# Module_I2C_Amiga_Floppy.net
KiCad netlist of a schematic drawn in EAGLE
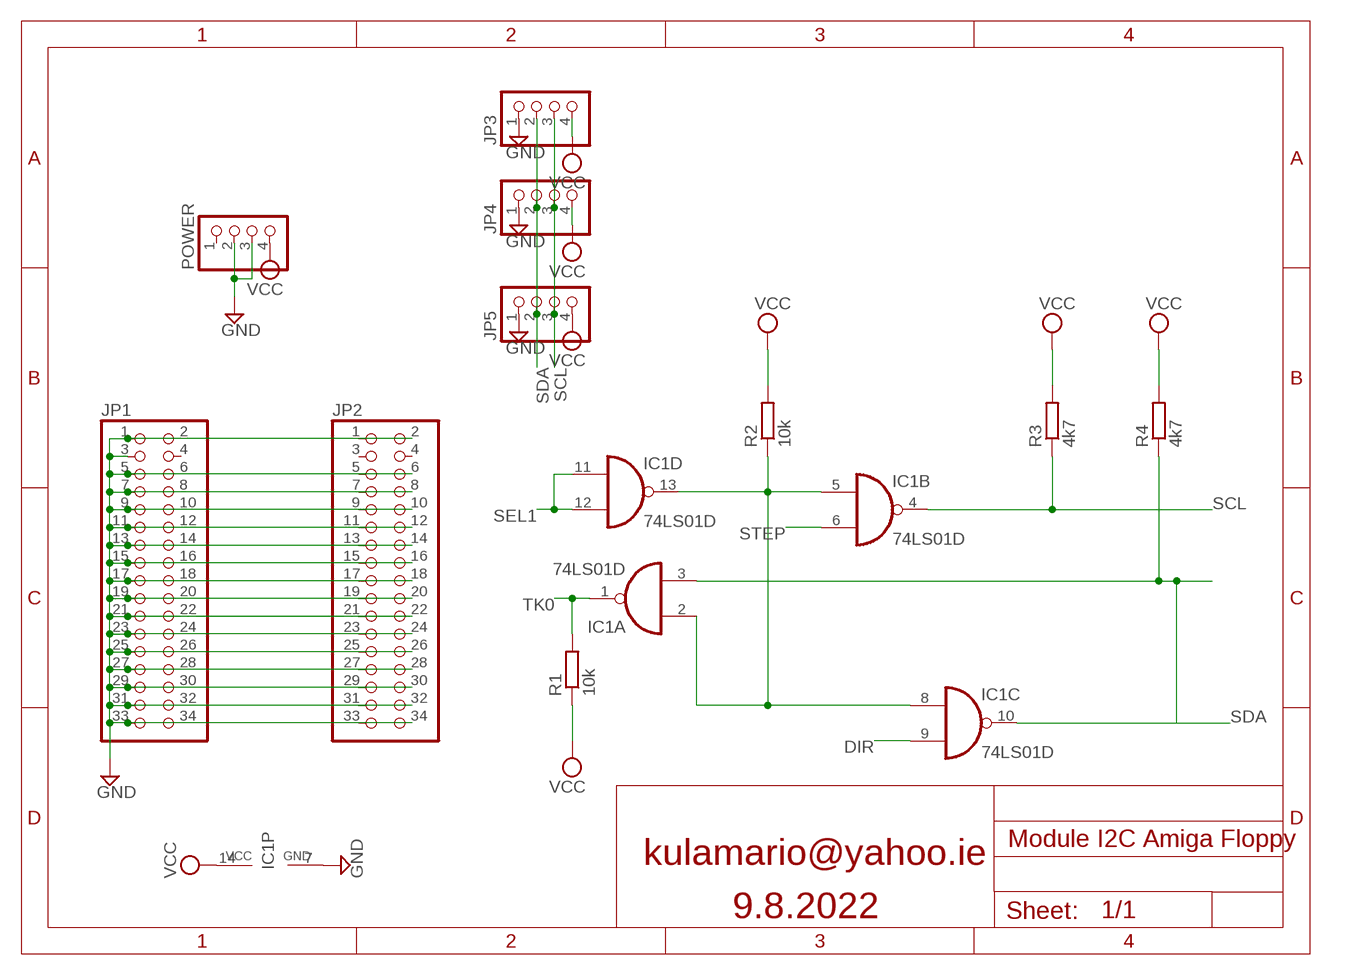
[diagram p0: schematic, sheet 1]

(export (version "E")
  (design (tool "Eeschema 10.0.6"))
  (components
    (comp (ref "IC1")
      (value "74LS01D")
      (footprint "eagle-import:SO14")
      (libsource (lib "eagle-import") (part "7401DLS"))
    )
    (comp (ref "JP1")
      (value "PINHD-2X17")
      (footprint "eagle-import:2X17")
      (libsource (lib "eagle-import") (part "PINHD-2X17"))
    )
    (comp (ref "JP2")
      (value "PINHD-2X17")
      (footprint "eagle-import:2X17")
      (libsource (lib "eagle-import") (part "PINHD-2X17"))
    )
    (comp (ref "JP3")
      (value "PINHD-1X4")
      (footprint "eagle-import:1X04")
      (libsource (lib "eagle-import") (part "PINHD-1X4"))
    )
    (comp (ref "JP4")
      (value "PINHD-1X4")
      (footprint "eagle-import:1X04")
      (libsource (lib "eagle-import") (part "PINHD-1X4"))
    )
    (comp (ref "JP5")
      (value "PINHD-1X4")
      (footprint "eagle-import:1X04")
      (libsource (lib "eagle-import") (part "PINHD-1X4"))
    )
    (comp (ref "POWER")
      (value "PINHD-1X4")
      (footprint "eagle-import:1X04")
      (libsource (lib "eagle-import") (part "PINHD-1X4"))
    )
    (comp (ref "R1")
      (value "10k")
      (footprint "eagle-import:R0805")
      (libsource (lib "eagle-import") (part "R-EU_R0805"))
    )
    (comp (ref "R2")
      (value "10k")
      (footprint "eagle-import:R0805")
      (libsource (lib "eagle-import") (part "R-EU_R0805"))
    )
    (comp (ref "R3")
      (value "4k7")
      (footprint "eagle-import:R0805")
      (libsource (lib "eagle-import") (part "R-EU_R0805"))
    )
    (comp (ref "R4")
      (value "4k7")
      (footprint "eagle-import:R0805")
      (libsource (lib "eagle-import") (part "R-EU_R0805"))
    )
  )
  (nets
    (net (code "1") (name "/DIR") (class "Default")
      (node (ref "IC1") (pin "9") (pinfunction "I1_9") (pintype "input"))
      (node (ref "JP1") (pin "18") (pinfunction "18_18") (pintype "passive"))
      (node (ref "JP2") (pin "18") (pinfunction "18_18") (pintype "passive"))
    )
    (net (code "2") (name "/SCL") (class "Default")
      (node (ref "IC1") (pin "4") (pinfunction "O_4") (pintype "open_collector"))
      (node (ref "JP3") (pin "3") (pinfunction "3_3") (pintype "passive"))
      (node (ref "JP4") (pin "3") (pinfunction "3_3") (pintype "passive"))
      (node (ref "JP5") (pin "3") (pinfunction "3_3") (pintype "passive"))
      (node (ref "R3") (pin "1") (pinfunction "1_1") (pintype "passive"))
    )
    (net (code "3") (name "/SDA") (class "Default")
      (node (ref "IC1") (pin "10") (pinfunction "O_10") (pintype "open_collector"))
      (node (ref "IC1") (pin "3") (pinfunction "I1_3") (pintype "input"))
      (node (ref "JP3") (pin "2") (pinfunction "2_2") (pintype "passive"))
      (node (ref "JP4") (pin "2") (pinfunction "2_2") (pintype "passive"))
      (node (ref "JP5") (pin "2") (pinfunction "2_2") (pintype "passive"))
      (node (ref "R4") (pin "1") (pinfunction "1_1") (pintype "passive"))
    )
    (net (code "4") (name "/SEL1") (class "Default")
      (node (ref "IC1") (pin "11") (pinfunction "I0_11") (pintype "input"))
      (node (ref "IC1") (pin "12") (pinfunction "I1_12") (pintype "input"))
      (node (ref "JP1") (pin "12") (pinfunction "12_12") (pintype "passive"))
      (node (ref "JP2") (pin "12") (pinfunction "12_12") (pintype "passive"))
    )
    (net (code "5") (name "/STEP") (class "Default")
      (node (ref "IC1") (pin "6") (pinfunction "I1_6") (pintype "input"))
      (node (ref "JP1") (pin "20") (pinfunction "20_20") (pintype "passive"))
      (node (ref "JP2") (pin "20") (pinfunction "20_20") (pintype "passive"))
    )
    (net (code "6") (name "/TK0") (class "Default")
      (node (ref "IC1") (pin "1") (pinfunction "O_1") (pintype "open_collector"))
      (node (ref "JP1") (pin "26") (pinfunction "26_26") (pintype "passive"))
      (node (ref "JP2") (pin "26") (pinfunction "26_26") (pintype "passive"))
      (node (ref "R1") (pin "2") (pinfunction "2_2") (pintype "passive"))
    )
    (net (code "7") (name "GND") (class "Default")
      (node (ref "IC1") (pin "7") (pinfunction "GND_7") (pintype "power_in"))
      (node (ref "JP1") (pin "1") (pinfunction "1_1") (pintype "passive"))
      (node (ref "JP1") (pin "11") (pinfunction "11_11") (pintype "passive"))
      (node (ref "JP1") (pin "13") (pinfunction "13_13") (pintype "passive"))
      (node (ref "JP1") (pin "15") (pinfunction "15_15") (pintype "passive"))
      (node (ref "JP1") (pin "17") (pinfunction "17_17") (pintype "passive"))
      (node (ref "JP1") (pin "19") (pinfunction "19_19") (pintype "passive"))
      (node (ref "JP1") (pin "21") (pinfunction "21_21") (pintype "passive"))
      (node (ref "JP1") (pin "23") (pinfunction "23_23") (pintype "passive"))
      (node (ref "JP1") (pin "25") (pinfunction "25_25") (pintype "passive"))
      (node (ref "JP1") (pin "27") (pinfunction "27_27") (pintype "passive"))
      (node (ref "JP1") (pin "29") (pinfunction "29_29") (pintype "passive"))
      (node (ref "JP1") (pin "3") (pinfunction "3_3") (pintype "passive"))
      (node (ref "JP1") (pin "31") (pinfunction "31_31") (pintype "passive"))
      (node (ref "JP1") (pin "33") (pinfunction "33_33") (pintype "passive"))
      (node (ref "JP1") (pin "5") (pinfunction "5_5") (pintype "passive"))
      (node (ref "JP1") (pin "7") (pinfunction "7_7") (pintype "passive"))
      (node (ref "JP1") (pin "9") (pinfunction "9_9") (pintype "passive"))
      (node (ref "JP2") (pin "1") (pinfunction "1_1") (pintype "passive"))
      (node (ref "JP2") (pin "11") (pinfunction "11_11") (pintype "passive"))
      (node (ref "JP2") (pin "13") (pinfunction "13_13") (pintype "passive"))
      (node (ref "JP2") (pin "15") (pinfunction "15_15") (pintype "passive"))
      (node (ref "JP2") (pin "17") (pinfunction "17_17") (pintype "passive"))
      (node (ref "JP2") (pin "19") (pinfunction "19_19") (pintype "passive"))
      (node (ref "JP2") (pin "21") (pinfunction "21_21") (pintype "passive"))
      (node (ref "JP2") (pin "23") (pinfunction "23_23") (pintype "passive"))
      (node (ref "JP2") (pin "25") (pinfunction "25_25") (pintype "passive"))
      (node (ref "JP2") (pin "27") (pinfunction "27_27") (pintype "passive"))
      (node (ref "JP2") (pin "29") (pinfunction "29_29") (pintype "passive"))
      (node (ref "JP2") (pin "31") (pinfunction "31_31") (pintype "passive"))
      (node (ref "JP2") (pin "33") (pinfunction "33_33") (pintype "passive"))
      (node (ref "JP2") (pin "5") (pinfunction "5_5") (pintype "passive"))
      (node (ref "JP2") (pin "7") (pinfunction "7_7") (pintype "passive"))
      (node (ref "JP2") (pin "9") (pinfunction "9_9") (pintype "passive"))
      (node (ref "JP3") (pin "1") (pinfunction "1_1") (pintype "passive"))
      (node (ref "JP4") (pin "1") (pinfunction "1_1") (pintype "passive"))
      (node (ref "JP5") (pin "1") (pinfunction "1_1") (pintype "passive"))
      (node (ref "POWER") (pin "2") (pinfunction "2_2") (pintype "passive"))
      (node (ref "POWER") (pin "3") (pinfunction "3_3") (pintype "passive"))
    )
    (net (code "8") (name "Net-(IC1A-I0)") (class "Default")
      (node (ref "IC1") (pin "13") (pinfunction "O_13") (pintype "open_collector"))
      (node (ref "IC1") (pin "2") (pinfunction "I0_2") (pintype "input"))
      (node (ref "IC1") (pin "5") (pinfunction "I0_5") (pintype "input"))
      (node (ref "IC1") (pin "8") (pinfunction "I0_8") (pintype "input"))
      (node (ref "R2") (pin "1") (pinfunction "1_1") (pintype "passive"))
    )
    (net (code "9") (name "Net-(JP1-Pad2)") (class "Default")
      (node (ref "JP1") (pin "2") (pinfunction "2_2") (pintype "passive"))
      (node (ref "JP2") (pin "2") (pinfunction "2_2") (pintype "passive"))
    )
    (net (code "10") (name "Net-(JP1-Pad6)") (class "Default")
      (node (ref "JP1") (pin "6") (pinfunction "6_6") (pintype "passive"))
      (node (ref "JP2") (pin "6") (pinfunction "6_6") (pintype "passive"))
    )
    (net (code "11") (name "Net-(JP1-Pad8)") (class "Default")
      (node (ref "JP1") (pin "8") (pinfunction "8_8") (pintype "passive"))
      (node (ref "JP2") (pin "8") (pinfunction "8_8") (pintype "passive"))
    )
    (net (code "12") (name "Net-(JP1-Pad10)") (class "Default")
      (node (ref "JP1") (pin "10") (pinfunction "10_10") (pintype "passive"))
      (node (ref "JP2") (pin "10") (pinfunction "10_10") (pintype "passive"))
    )
    (net (code "13") (name "Net-(JP1-Pad14)") (class "Default")
      (node (ref "JP1") (pin "14") (pinfunction "14_14") (pintype "passive"))
      (node (ref "JP2") (pin "14") (pinfunction "14_14") (pintype "passive"))
    )
    (net (code "14") (name "Net-(JP1-Pad16)") (class "Default")
      (node (ref "JP1") (pin "16") (pinfunction "16_16") (pintype "passive"))
      (node (ref "JP2") (pin "16") (pinfunction "16_16") (pintype "passive"))
    )
    (net (code "15") (name "Net-(JP1-Pad22)") (class "Default")
      (node (ref "JP1") (pin "22") (pinfunction "22_22") (pintype "passive"))
      (node (ref "JP2") (pin "22") (pinfunction "22_22") (pintype "passive"))
    )
    (net (code "16") (name "Net-(JP1-Pad24)") (class "Default")
      (node (ref "JP1") (pin "24") (pinfunction "24_24") (pintype "passive"))
      (node (ref "JP2") (pin "24") (pinfunction "24_24") (pintype "passive"))
    )
    (net (code "17") (name "Net-(JP1-Pad28)") (class "Default")
      (node (ref "JP1") (pin "28") (pinfunction "28_28") (pintype "passive"))
      (node (ref "JP2") (pin "28") (pinfunction "28_28") (pintype "passive"))
    )
    (net (code "18") (name "Net-(JP1-Pad30)") (class "Default")
      (node (ref "JP1") (pin "30") (pinfunction "30_30") (pintype "passive"))
      (node (ref "JP2") (pin "30") (pinfunction "30_30") (pintype "passive"))
    )
    (net (code "19") (name "Net-(JP1-Pad32)") (class "Default")
      (node (ref "JP1") (pin "32") (pinfunction "32_32") (pintype "passive"))
      (node (ref "JP2") (pin "32") (pinfunction "32_32") (pintype "passive"))
    )
    (net (code "20") (name "Net-(JP1-Pad34)") (class "Default")
      (node (ref "JP1") (pin "34") (pinfunction "34_34") (pintype "passive"))
      (node (ref "JP2") (pin "34") (pinfunction "34_34") (pintype "passive"))
    )
    (net (code "21") (name "VCC") (class "Default")
      (node (ref "IC1") (pin "14") (pinfunction "VCC_14") (pintype "power_in"))
      (node (ref "JP3") (pin "4") (pinfunction "4_4") (pintype "passive"))
      (node (ref "JP4") (pin "4") (pinfunction "4_4") (pintype "passive"))
      (node (ref "JP5") (pin "4") (pinfunction "4_4") (pintype "passive"))
      (node (ref "POWER") (pin "4") (pinfunction "4_4") (pintype "passive"))
      (node (ref "R1") (pin "1") (pinfunction "1_1") (pintype "passive"))
      (node (ref "R2") (pin "2") (pinfunction "2_2") (pintype "passive"))
      (node (ref "R3") (pin "2") (pinfunction "2_2") (pintype "passive"))
      (node (ref "R4") (pin "2") (pinfunction "2_2") (pintype "passive"))
    )
    (net (code "22") (name "unconnected-(JP1-Pad4)") (class "Default")
      (node (ref "JP1") (pin "4") (pinfunction "4_4") (pintype "passive"))
    )
    (net (code "23") (name "unconnected-(JP2-Pad3)") (class "Default")
      (node (ref "JP2") (pin "3") (pinfunction "3_3") (pintype "passive"))
    )
    (net (code "24") (name "unconnected-(JP2-Pad4)") (class "Default")
      (node (ref "JP2") (pin "4") (pinfunction "4_4") (pintype "passive"))
    )
    (net (code "25") (name "unconnected-(POWER-Pad1)") (class "Default")
      (node (ref "POWER") (pin "1") (pinfunction "1_1") (pintype "passive"))
    )
  )
)
